# Graphic_LCD_Backpack-v15.net
KiCad netlist of a schematic drawn in EAGLE
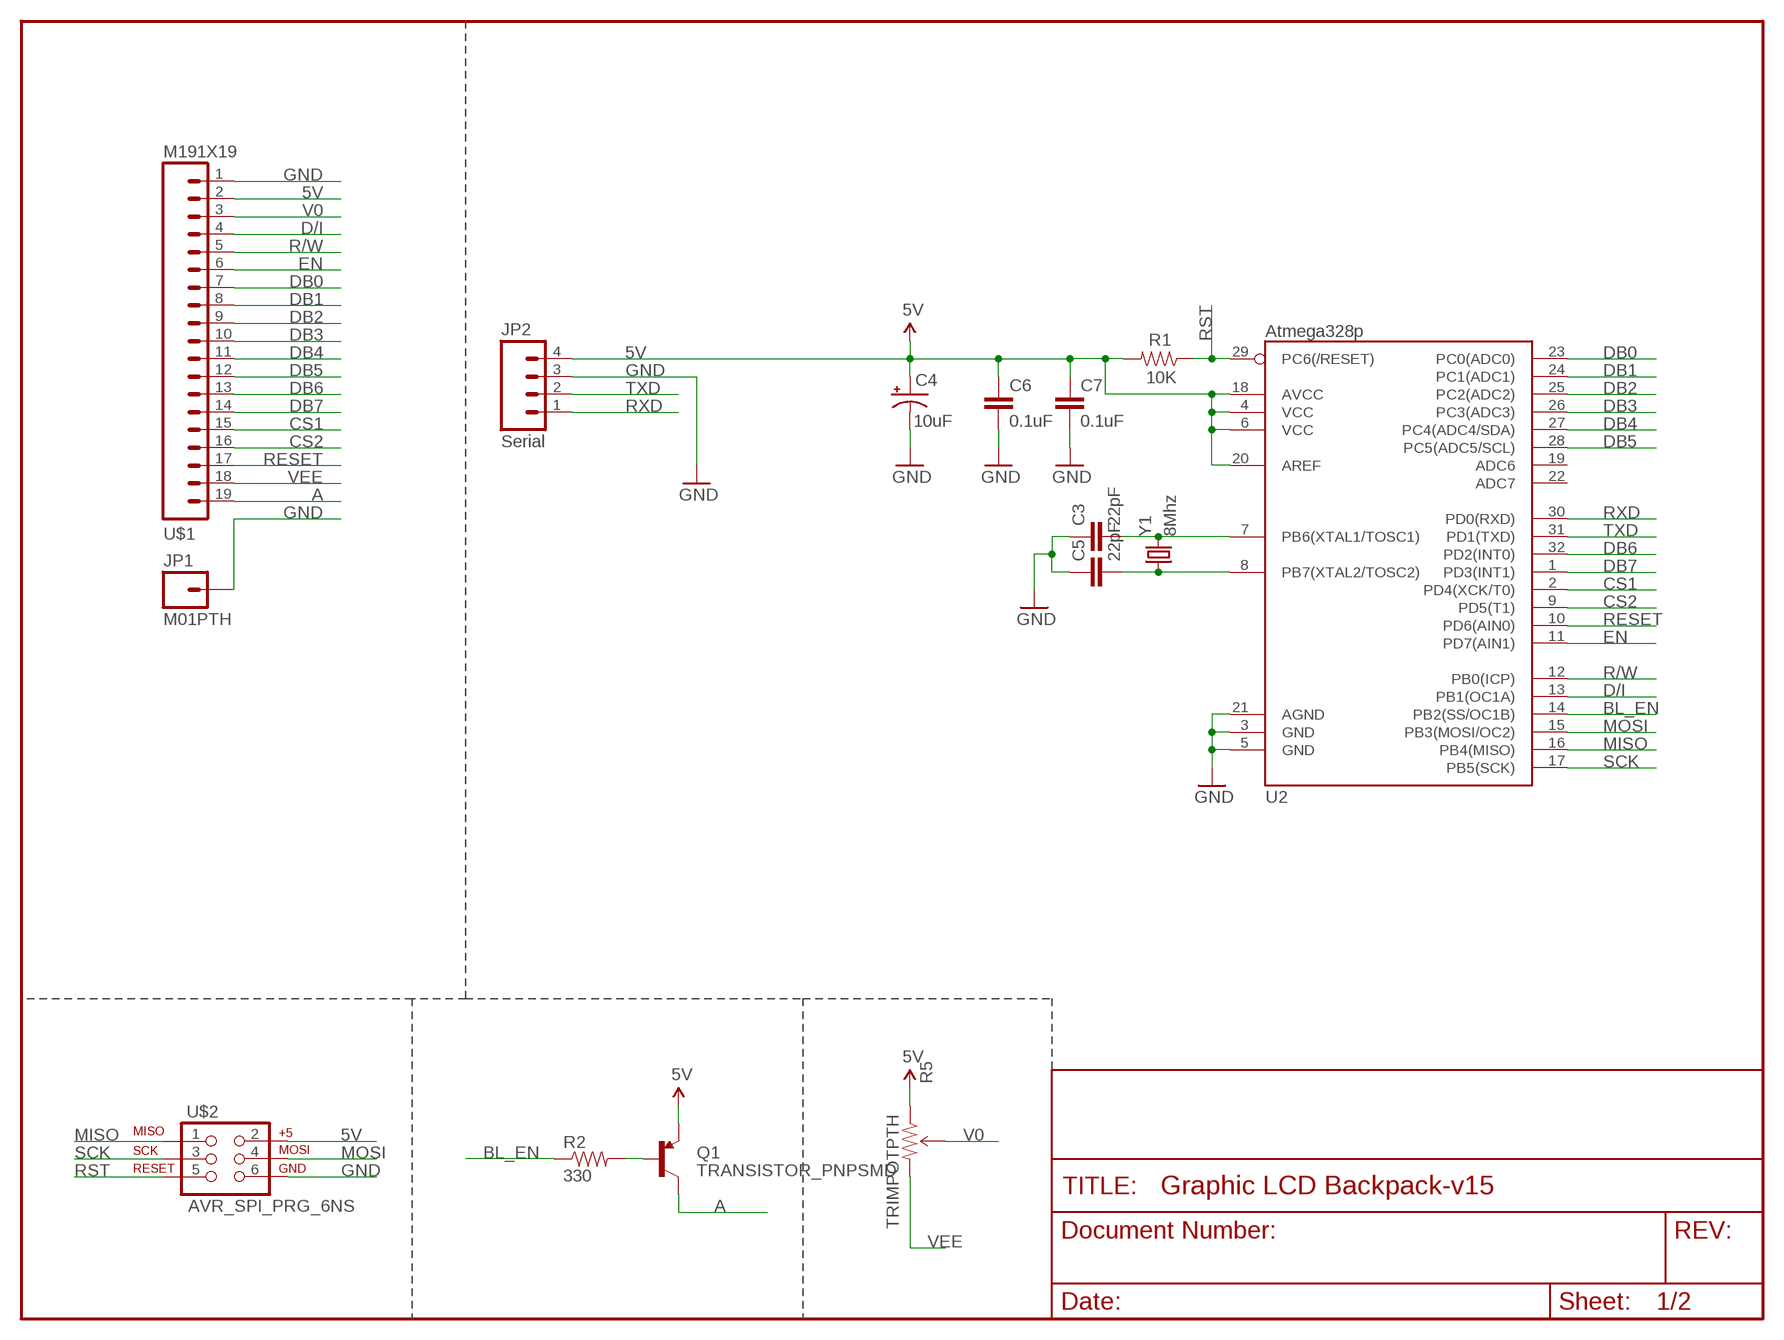
[diagram p0: schematic, sheet 1]

(export (version "E")
  (design (tool "Eeschema 10.0.6"))
  (components
    (comp (ref "C3")
      (value "22pF")
      (footprint "eagle-import:1206")
      (libsource (lib "eagle-import") (part "CAP1206"))
    )
    (comp (ref "C4")
      (value "10uF")
      (footprint "eagle-import:EIA3216")
      (libsource (lib "eagle-import") (part "CAP_POL1206"))
    )
    (comp (ref "C5")
      (value "22pF")
      (footprint "eagle-import:1206")
      (libsource (lib "eagle-import") (part "CAP1206"))
    )
    (comp (ref "C6")
      (value "0.1uF")
      (footprint "eagle-import:1206")
      (libsource (lib "eagle-import") (part "CAP1206"))
    )
    (comp (ref "C7")
      (value "0.1uF")
      (footprint "eagle-import:1206")
      (libsource (lib "eagle-import") (part "CAP1206"))
    )
    (comp (ref "JP1")
      (value "M01PTH")
      (footprint "eagle-import:1X01")
      (libsource (lib "eagle-import") (part "M01PTH"))
    )
    (comp (ref "JP2")
      (value "Serial")
      (footprint "eagle-import:1X04")
      (libsource (lib "eagle-import") (part "M04PTH"))
    )
    (comp (ref "Q1")
      (value "TRANSISTOR_PNPSMD")
      (footprint "eagle-import:SOT23-3")
      (libsource (lib "eagle-import") (part "TRANSISTOR_PNPSMD"))
    )
    (comp (ref "R1")
      (value "10K")
      (footprint "eagle-import:0805")
      (libsource (lib "eagle-import") (part "RESISTOR"))
    )
    (comp (ref "R2")
      (value "330")
      (footprint "eagle-import:0805")
      (libsource (lib "eagle-import") (part "RESISTOR"))
    )
    (comp (ref "R5")
      (value "TRIMPOTPTH")
      (footprint "eagle-import:TRIM_POT_PTH")
      (libsource (lib "eagle-import") (part "TRIMPOTPTH"))
    )
    (comp (ref "U$1")
      (value "M191X19")
      (footprint "eagle-import:1X19")
      (libsource (lib "eagle-import") (part "M191X19"))
    )
    (comp (ref "U$2")
      (value "AVR_SPI_PRG_6NS")
      (footprint "eagle-import:2X3-NS")
      (libsource (lib "eagle-import") (part "AVR_SPI_PRG_6NS"))
    )
    (comp (ref "U2")
      (value "Atmega328p")
      (footprint "eagle-import:TQFP32-08")
      (libsource (lib "eagle-import") (part "ATMEGA328_SMT"))
    )
    (comp (ref "Y1")
      (value "8Mhz")
      (footprint "eagle-import:HC49US")
      (libsource (lib "eagle-import") (part "CRYSTALHC49US"))
    )
  )
  (nets
    (net (code "1") (name "5V") (class "Default")
      (node (ref "C4") (pin "A") (pinfunction "+_A") (pintype "passive"))
      (node (ref "C6") (pin "1") (pinfunction "1_1") (pintype "passive"))
      (node (ref "C7") (pin "1") (pinfunction "1_1") (pintype "passive"))
      (node (ref "JP2") (pin "4") (pinfunction "4_4") (pintype "passive"))
      (node (ref "Q1") (pin "2") (pinfunction "E_2") (pintype "passive"))
      (node (ref "R1") (pin "2") (pinfunction "2_2") (pintype "passive"))
      (node (ref "R5") (pin "1") (pinfunction "CCW_1") (pintype "passive"))
      (node (ref "U$1") (pin "2") (pinfunction "2_2") (pintype "passive"))
      (node (ref "U$2") (pin "2") (pinfunction "2_2") (pintype "passive"))
      (node (ref "U2") (pin "18") (pinfunction "AVCC_18") (pintype "bidirectional"))
      (node (ref "U2") (pin "20") (pinfunction "AREF_20") (pintype "bidirectional"))
      (node (ref "U2") (pin "4") (pinfunction "VCC_4") (pintype "bidirectional"))
      (node (ref "U2") (pin "6") (pinfunction "VCC_6") (pintype "bidirectional"))
    )
    (net (code "2") (name "A") (class "Default")
      (node (ref "Q1") (pin "3") (pinfunction "C_3") (pintype "passive"))
      (node (ref "U$1") (pin "19") (pinfunction "19_19") (pintype "passive"))
    )
    (net (code "3") (name "BL_EN") (class "Default")
      (node (ref "R2") (pin "1") (pinfunction "1_1") (pintype "passive"))
      (node (ref "U2") (pin "14") (pinfunction "PB2(SS/OC1B)_14") (pintype "bidirectional"))
    )
    (net (code "4") (name "CS1") (class "Default")
      (node (ref "U$1") (pin "15") (pinfunction "15_15") (pintype "passive"))
      (node (ref "U2") (pin "2") (pinfunction "PD4(XCK/T0)_2") (pintype "bidirectional"))
    )
    (net (code "5") (name "CS2") (class "Default")
      (node (ref "U$1") (pin "16") (pinfunction "16_16") (pintype "passive"))
      (node (ref "U2") (pin "9") (pinfunction "PD5(T1)_9") (pintype "bidirectional"))
    )
    (net (code "6") (name "DB0") (class "Default")
      (node (ref "U$1") (pin "7") (pinfunction "7_7") (pintype "passive"))
      (node (ref "U2") (pin "23") (pinfunction "PC0(ADC0)_23") (pintype "bidirectional"))
    )
    (net (code "7") (name "DB1") (class "Default")
      (node (ref "U$1") (pin "8") (pinfunction "8_8") (pintype "passive"))
      (node (ref "U2") (pin "24") (pinfunction "PC1(ADC1)_24") (pintype "bidirectional"))
    )
    (net (code "8") (name "DB2") (class "Default")
      (node (ref "U$1") (pin "9") (pinfunction "9_9") (pintype "passive"))
      (node (ref "U2") (pin "25") (pinfunction "PC2(ADC2)_25") (pintype "bidirectional"))
    )
    (net (code "9") (name "DB3") (class "Default")
      (node (ref "U$1") (pin "10") (pinfunction "10_10") (pintype "passive"))
      (node (ref "U2") (pin "26") (pinfunction "PC3(ADC3)_26") (pintype "bidirectional"))
    )
    (net (code "10") (name "DB4") (class "Default")
      (node (ref "U$1") (pin "11") (pinfunction "11_11") (pintype "passive"))
      (node (ref "U2") (pin "27") (pinfunction "PC4(ADC4/SDA)_27") (pintype "bidirectional"))
    )
    (net (code "11") (name "DB5") (class "Default")
      (node (ref "U$1") (pin "12") (pinfunction "12_12") (pintype "passive"))
      (node (ref "U2") (pin "28") (pinfunction "PC5(ADC5/SCL)_28") (pintype "bidirectional"))
    )
    (net (code "12") (name "DB6") (class "Default")
      (node (ref "U$1") (pin "13") (pinfunction "13_13") (pintype "passive"))
      (node (ref "U2") (pin "32") (pinfunction "PD2(INT0)_32") (pintype "bidirectional"))
    )
    (net (code "13") (name "DB7") (class "Default")
      (node (ref "U$1") (pin "14") (pinfunction "14_14") (pintype "passive"))
      (node (ref "U2") (pin "1") (pinfunction "PD3(INT1)_1") (pintype "bidirectional"))
    )
    (net (code "14") (name "D{slash}I") (class "Default")
      (node (ref "U$1") (pin "4") (pinfunction "4_4") (pintype "passive"))
      (node (ref "U2") (pin "13") (pinfunction "PB1(OC1A)_13") (pintype "bidirectional"))
    )
    (net (code "15") (name "EN") (class "Default")
      (node (ref "U$1") (pin "6") (pinfunction "6_6") (pintype "passive"))
      (node (ref "U2") (pin "11") (pinfunction "PD7(AIN1)_11") (pintype "bidirectional"))
    )
    (net (code "16") (name "GND") (class "Default")
      (node (ref "C3") (pin "1") (pinfunction "1_1") (pintype "passive"))
      (node (ref "C4") (pin "C") (pinfunction "-_C") (pintype "passive"))
      (node (ref "C5") (pin "1") (pinfunction "1_1") (pintype "passive"))
      (node (ref "C6") (pin "2") (pinfunction "2_2") (pintype "passive"))
      (node (ref "C7") (pin "2") (pinfunction "2_2") (pintype "passive"))
      (node (ref "JP1") (pin "1") (pinfunction "1_1") (pintype "passive"))
      (node (ref "JP2") (pin "3") (pinfunction "3_3") (pintype "passive"))
      (node (ref "U$1") (pin "1") (pinfunction "1_1") (pintype "passive"))
      (node (ref "U$2") (pin "6") (pinfunction "6_6") (pintype "passive"))
      (node (ref "U2") (pin "21") (pinfunction "AGND_21") (pintype "bidirectional"))
      (node (ref "U2") (pin "3") (pinfunction "GND_3") (pintype "bidirectional"))
      (node (ref "U2") (pin "5") (pinfunction "GND_5") (pintype "bidirectional"))
    )
    (net (code "17") (name "MISO") (class "Default")
      (node (ref "U$2") (pin "1") (pinfunction "1_1") (pintype "passive"))
      (node (ref "U2") (pin "16") (pinfunction "PB4(MISO)_16") (pintype "bidirectional"))
    )
    (net (code "18") (name "MOSI") (class "Default")
      (node (ref "U$2") (pin "4") (pinfunction "4_4") (pintype "passive"))
      (node (ref "U2") (pin "15") (pinfunction "PB3(MOSI/OC2)_15") (pintype "bidirectional"))
    )
    (net (code "19") (name "Net-(Q1-B)") (class "Default")
      (node (ref "Q1") (pin "1") (pinfunction "B_1") (pintype "passive"))
      (node (ref "R2") (pin "2") (pinfunction "2_2") (pintype "passive"))
    )
    (net (code "20") (name "Net-(U2-PB6(XTAL1{slash}TOSC1))") (class "Default")
      (node (ref "C3") (pin "2") (pinfunction "2_2") (pintype "passive"))
      (node (ref "U2") (pin "7") (pinfunction "PB6(XTAL1/TOSC1)_7") (pintype "bidirectional"))
      (node (ref "Y1") (pin "2") (pinfunction "2_2") (pintype "passive"))
    )
    (net (code "21") (name "Net-(U2-PB7(XTAL2{slash}TOSC2))") (class "Default")
      (node (ref "C5") (pin "2") (pinfunction "2_2") (pintype "passive"))
      (node (ref "U2") (pin "8") (pinfunction "PB7(XTAL2/TOSC2)_8") (pintype "bidirectional"))
      (node (ref "Y1") (pin "1") (pinfunction "1_1") (pintype "passive"))
    )
    (net (code "22") (name "RESET") (class "Default")
      (node (ref "U$1") (pin "17") (pinfunction "17_17") (pintype "passive"))
      (node (ref "U2") (pin "10") (pinfunction "PD6(AIN0)_10") (pintype "bidirectional"))
    )
    (net (code "23") (name "RST") (class "Default")
      (node (ref "R1") (pin "1") (pinfunction "1_1") (pintype "passive"))
      (node (ref "U$2") (pin "5") (pinfunction "5_5") (pintype "passive"))
      (node (ref "U2") (pin "29") (pinfunction "PC6(/RESET)_29") (pintype "bidirectional"))
    )
    (net (code "24") (name "RXD") (class "Default")
      (node (ref "JP2") (pin "1") (pinfunction "1_1") (pintype "passive"))
      (node (ref "U2") (pin "30") (pinfunction "PD0(RXD)_30") (pintype "bidirectional"))
    )
    (net (code "25") (name "R{slash}W") (class "Default")
      (node (ref "U$1") (pin "5") (pinfunction "5_5") (pintype "passive"))
      (node (ref "U2") (pin "12") (pinfunction "PB0(ICP)_12") (pintype "bidirectional"))
    )
    (net (code "26") (name "SCK") (class "Default")
      (node (ref "U$2") (pin "3") (pinfunction "3_3") (pintype "passive"))
      (node (ref "U2") (pin "17") (pinfunction "PB5(SCK)_17") (pintype "bidirectional"))
    )
    (net (code "27") (name "TXD") (class "Default")
      (node (ref "JP2") (pin "2") (pinfunction "2_2") (pintype "passive"))
      (node (ref "U2") (pin "31") (pinfunction "PD1(TXD)_31") (pintype "bidirectional"))
    )
    (net (code "28") (name "V0") (class "Default")
      (node (ref "R5") (pin "2") (pinfunction "WIPER_2") (pintype "passive"))
      (node (ref "U$1") (pin "3") (pinfunction "3_3") (pintype "passive"))
    )
    (net (code "29") (name "VEE") (class "Default")
      (node (ref "R5") (pin "3") (pinfunction "CW_3") (pintype "passive"))
      (node (ref "U$1") (pin "18") (pinfunction "18_18") (pintype "passive"))
    )
    (net (code "30") (name "unconnected-(U2-ADC6-Pad19)") (class "Default")
      (node (ref "U2") (pin "19") (pinfunction "ADC6_19") (pintype "bidirectional"))
    )
    (net (code "31") (name "unconnected-(U2-ADC7-Pad22)") (class "Default")
      (node (ref "U2") (pin "22") (pinfunction "ADC7_22") (pintype "bidirectional"))
    )
  )
)
